# POWER_SUPPLY.net
KiCad netlist of a schematic drawn in Altium Designer
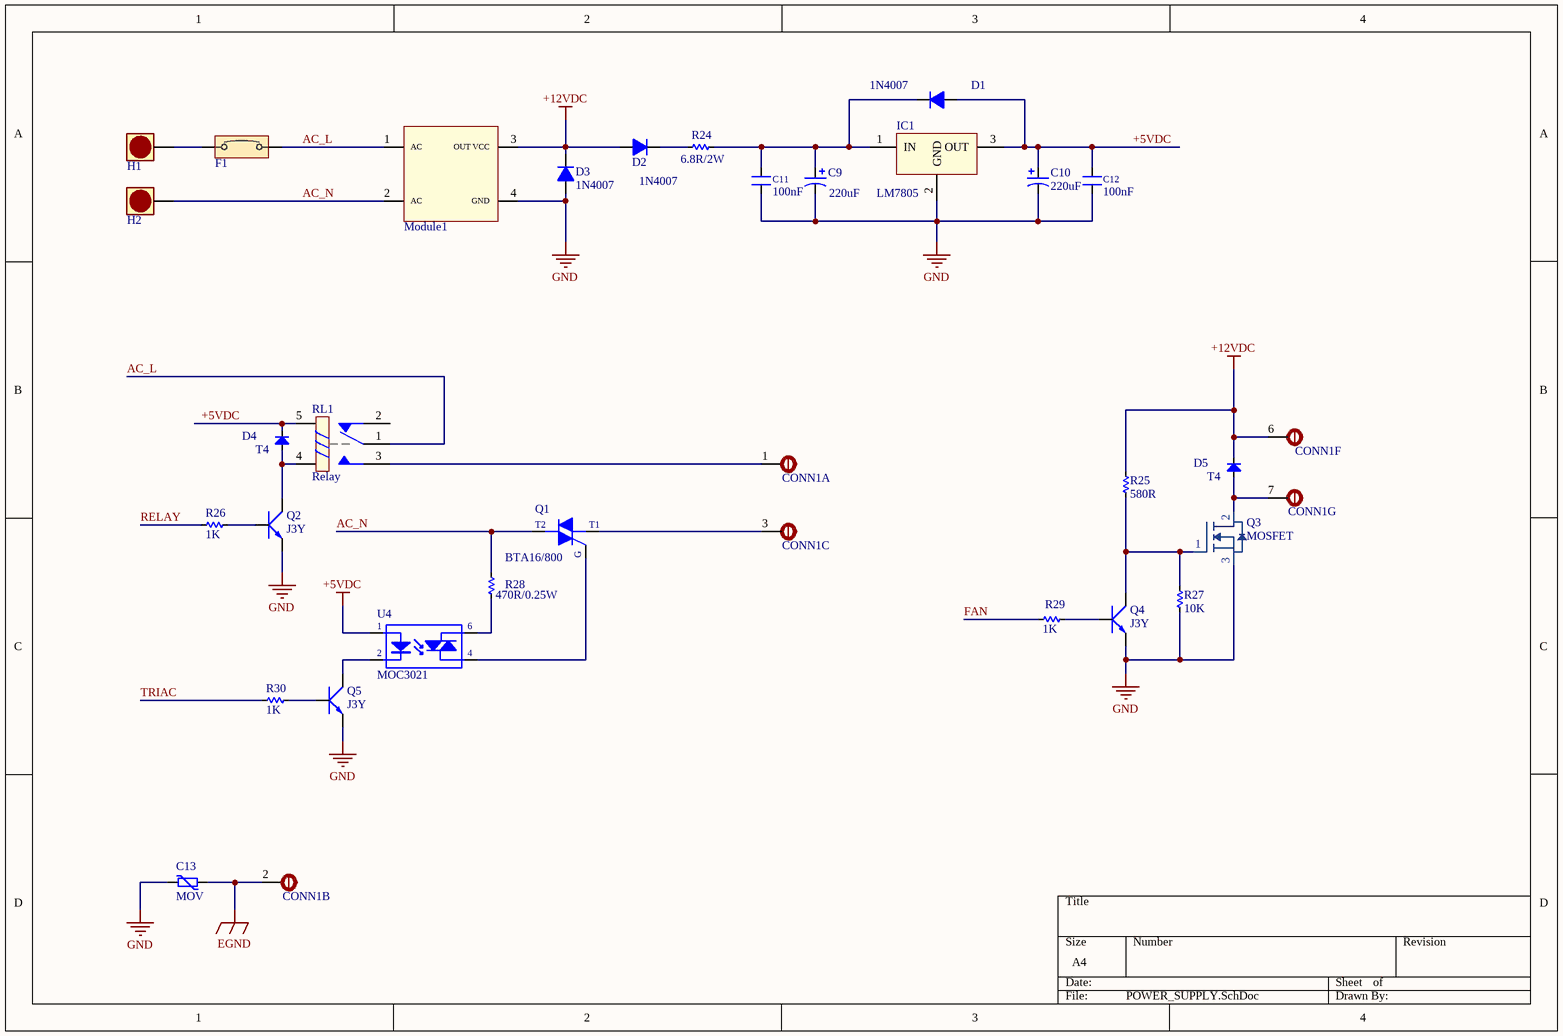
[diagram p0: POWER_SUPPLY.SchDoc]

(export (version "E")
  (design (tool "Eeschema 10.0.6"))
  (components
    (comp (ref "C9")
      (value "220uF")
      (footprint "C8MM")
      (description "CAP-Radial")
      (fields (field (name "PUBLISHER") "Altium Limited"))
      (libsource (lib "") (part "CAP-Radial_1"))
    )
    (comp (ref "C10")
      (value "220uF")
      (footprint "C8MM")
      (description "CAP-Radial")
      (fields (field (name "PUBLISHER") "Altium Limited"))
      (libsource (lib "Sang_Library") (part "CAP-Radial"))
    )
    (comp (ref "C11")
      (value "100nF")
      (footprint "SM-Cap-1206")
      (description "CAP SMD")
      (fields (field (name "DESIGNED BY") "VanDungEvn"))
      (libsource (lib "Sang_Library") (part "CAP SMD"))
    )
    (comp (ref "C12")
      (value "100nF")
      (footprint "SM-Cap-1206")
      (description "CAP SMD")
      (fields (field (name "DESIGNED BY") "VanDungEvn"))
      (libsource (lib "Sang_Library") (part "CAP SMD"))
    )
    (comp (ref "C13") (value "MOV") (footprint "14D271K") (libsource (lib "Huan") (part "MOV")))
    (comp (ref "CONN1")
      (value "GX-16 CONNECTOR")
      (footprint "GX-16")
      (libsource (lib "") (part "GX-16 CONNECTOR_4"))
    )
    (comp (ref "D1")
      (value "1N4007")
      (footprint "DO-213AA")
      (description "Diode 1A")
      (libsource (lib "Sang_Library") (part "Diode  1N4007"))
    )
    (comp (ref "D2")
      (value "1N4007")
      (footprint "DO-213AA")
      (description "Diode 1A")
      (libsource (lib "Sang_Library") (part "Diode  1N4007"))
    )
    (comp (ref "D3")
      (value "1N4007")
      (footprint "DO-213AA")
      (description "Diode 1A")
      (libsource (lib "Sang_Library") (part "Diode  1N4007"))
    )
    (comp (ref "D4")
      (value "T4")
      (footprint "SOD123")
      (description "Default Diode")
      (fields (field (name "PUBLISHER") "Altium Limited"))
      (libsource (lib "Sang_Library") (part "Diode-1N4007 -A4"))
    )
    (comp (ref "D5")
      (value "T4")
      (footprint "SOD123")
      (description "Default Diode")
      (fields (field (name "PUBLISHER") "Altium Limited"))
      (libsource (lib "Sang_Library") (part "Diode-1N4007 -A4"))
    )
    (comp (ref "F1") (value "FUSE") (footprint "FUSE 5X20MM") (libsource (lib "Huan") (part "FUSE")))
    (comp (ref "H1") (value "JP1P") (footprint "PW-JP") (libsource (lib "Huan") (part "JP1P")))
    (comp (ref "H2") (value "JP1P") (footprint "PW-JP") (libsource (lib "Huan") (part "JP1P")))
    (comp (ref "IC1")
      (value "LM7805")
      (footprint "QTO-220H3")
      (description "On ap +, from + 5 to + 24VDC")
      (libsource (lib "Sang_Library") (part "LM78xx"))
    )
    (comp (ref "Module1")
      (value "AC DC Powersupply")
      (footprint "VNPT_ADAPTER")
      (libsource (lib "Huan") (part "AC DC Powersupply"))
    )
    (comp (ref "Q1")
      (value "BTA16/800")
      (footprint "TO220H2")
      (description "Silicon Bidirectional Triode Thyristor")
      (fields (field (name "PUBLISHER") "Altium Limited"))
      (libsource (lib "Sang_Library") (part "BTA12-600_TRIAC"))
    )
    (comp (ref "Q2")
      (value "J3Y")
      (footprint "SOT23B")
      (description "NPN 600mW, ECB")
      (libsource (lib "Sang_Library") (part "2N222"))
    )
    (comp (ref "Q3")
      (value "MOSFET")
      (footprint "TO-252")
      (description "MOSFET N chane")
      (libsource (lib "Huan") (part "MOSFET-N"))
    )
    (comp (ref "Q4")
      (value "J3Y")
      (footprint "SOT23B")
      (description "NPN 600mW, ECB")
      (libsource (lib "Sang_Library") (part "2N222"))
    )
    (comp (ref "Q5")
      (value "J3Y")
      (footprint "SOT23B")
      (description "NPN 600mW, ECB")
      (libsource (lib "Sang_Library") (part "2N222"))
    )
    (comp (ref "R24")
      (value "6.8R/2W")
      (footprint "R2WD")
      (description "Res")
      (fields
        (field (name "MANUFACTURER") "Generic Components")
        (field (name "PUBLISHER") "Altium Hobart Technology Centre")
      )
      (libsource (lib "Sang_Library") (part "Res_DIP"))
    )
    (comp (ref "R25")
      (value "580R")
      (footprint "RES-SMD-0805")
      (description "Resistor")
      (fields
        (field (name "MANUFACTURER") "Generic Components")
        (field (name "PUBLISHER") "Altium Hobart Technology Centre")
      )
      (libsource (lib "Sang_Library") (part "Res-SMD"))
    )
    (comp (ref "R26")
      (value "1K")
      (footprint "RES-SMD-0805")
      (description "Resistor")
      (fields
        (field (name "MANUFACTURER") "Generic Components")
        (field (name "PUBLISHER") "Altium Hobart Technology Centre")
      )
      (libsource (lib "Sang_Library") (part "Res-SMD"))
    )
    (comp (ref "R27")
      (value "10K")
      (footprint "RES-SMD-0603")
      (description "Resistor")
      (fields
        (field (name "MANUFACTURER") "Generic Components")
        (field (name "PUBLISHER") "Altium Hobart Technology Centre")
      )
      (libsource (lib "Sang_Library") (part "Res-SMD"))
    )
    (comp (ref "R28")
      (value "470R/0.25W")
      (footprint "RES-1/4W")
      (description "Res")
      (fields
        (field (name "MANUFACTURER") "Generic Components")
        (field (name "PUBLISHER") "Altium Hobart Technology Centre")
      )
      (libsource (lib "Sang_Library") (part "Res_DIP"))
    )
    (comp (ref "R29")
      (value "1K")
      (footprint "RES-SMD-0805")
      (description "Resistor")
      (fields
        (field (name "MANUFACTURER") "Generic Components")
        (field (name "PUBLISHER") "Altium Hobart Technology Centre")
      )
      (libsource (lib "Sang_Library") (part "Res-SMD"))
    )
    (comp (ref "R30")
      (value "1K")
      (footprint "RES-SMD-0805")
      (description "Resistor")
      (fields
        (field (name "MANUFACTURER") "Generic Components")
        (field (name "PUBLISHER") "Altium Hobart Technology Centre")
      )
      (libsource (lib "Sang_Library") (part "Res-SMD"))
    )
    (comp (ref "RL1")
      (value "Relay")
      (footprint "RL-05VDC-10A")
      (description "Relay SPDT 5 Pin")
      (libsource (lib "Sang_Library") (part "Relay 5VDC"))
    )
    (comp (ref "U4")
      (value "MOC3021")
      (footprint "DIP6/W0.3 - MOC3021")
      (description "Single Opto")
      (libsource (lib "Sang_Library") (part "MOC3021"))
    )
  )
  (nets
    (net (code "1") (name "+5VDC") (class "Default")
      (node (ref "C10") (pin "1") (pinfunction "1_1") (pintype "passive"))
      (node (ref "C12") (pin "1") (pinfunction "1_1") (pintype "passive"))
      (node (ref "D1") (pin "1") (pinfunction "1_1") (pintype "passive"))
      (node (ref "D4") (pin "K") (pinfunction "K_K") (pintype "passive"))
      (node (ref "IC1") (pin "3") (pinfunction "OUT_3") (pintype "passive"))
      (node (ref "RL1") (pin "5") (pinfunction "5_5") (pintype "passive"))
      (node (ref "U4") (pin "1") (pinfunction "A_1") (pintype "passive"))
    )
    (net (code "2") (name "+12VDC") (class "Default")
      (node (ref "CONN1") (pin "6") (pinfunction "6_6") (pintype "passive"))
      (node (ref "D2") (pin "1") (pinfunction "1_1") (pintype "passive"))
      (node (ref "D3") (pin "2") (pinfunction "2_2") (pintype "passive"))
      (node (ref "D5") (pin "K") (pinfunction "K_K") (pintype "passive"))
      (node (ref "Module1") (pin "3") (pinfunction "OUT_VCC_3") (pintype "passive"))
      (node (ref "R25") (pin "1") (pinfunction "1_1") (pintype "passive"))
    )
    (net (code "3") (name "/AC_L") (class "Default")
      (node (ref "F1") (pin "2") (pinfunction "2_2") (pintype "passive"))
      (node (ref "Module1") (pin "1") (pinfunction "AC_1") (pintype "passive"))
      (node (ref "RL1") (pin "1") (pinfunction "1_1") (pintype "passive"))
    )
    (net (code "4") (name "/AC_N") (class "Default")
      (node (ref "H2") (pin "1") (pinfunction "1_1") (pintype "passive"))
      (node (ref "Module1") (pin "2") (pinfunction "AC_2") (pintype "passive"))
      (node (ref "Q1") (pin "2") (pinfunction "M2_2") (pintype "passive"))
      (node (ref "R28") (pin "1") (pinfunction "1_1") (pintype "passive"))
    )
    (net (code "5") (name "/FAN") (class "Default")
      (node (ref "R29") (pin "2") (pinfunction "2_2") (pintype "passive"))
    )
    (net (code "6") (name "/RELAY") (class "Default")
      (node (ref "R26") (pin "2") (pinfunction "2_2") (pintype "passive"))
    )
    (net (code "7") (name "/TRIAC") (class "Default")
      (node (ref "R30") (pin "2") (pinfunction "2_2") (pintype "passive"))
    )
    (net (code "8") (name "EGND") (class "Default")
      (node (ref "C13") (pin "1") (pinfunction "1_1") (pintype "passive"))
      (node (ref "CONN1") (pin "2") (pinfunction "2_2") (pintype "passive"))
    )
    (net (code "9") (name "GND") (class "Default")
      (node (ref "C10") (pin "2") (pinfunction "2_2") (pintype "passive"))
      (node (ref "C11") (pin "2") (pinfunction "2_2") (pintype "passive"))
      (node (ref "C12") (pin "2") (pinfunction "2_2") (pintype "passive"))
      (node (ref "C13") (pin "2") (pinfunction "2_2") (pintype "passive"))
      (node (ref "C9") (pin "2") (pinfunction "2_2") (pintype "passive"))
      (node (ref "D3") (pin "1") (pinfunction "1_1") (pintype "passive"))
      (node (ref "IC1") (pin "2") (pinfunction "GND_2") (pintype "passive"))
      (node (ref "Module1") (pin "4") (pinfunction "GND_4") (pintype "passive"))
      (node (ref "Q2") (pin "1") (pinfunction "E_1") (pintype "passive"))
      (node (ref "Q3") (pin "3") (pinfunction "3_3") (pintype "passive"))
      (node (ref "Q4") (pin "1") (pinfunction "E_1") (pintype "passive"))
      (node (ref "Q5") (pin "1") (pinfunction "E_1") (pintype "passive"))
      (node (ref "R27") (pin "2") (pinfunction "2_2") (pintype "passive"))
    )
    (net (code "10") (name "Net-(CONN1-Pad1)") (class "Default")
      (node (ref "CONN1") (pin "1") (pinfunction "1_1") (pintype "passive"))
      (node (ref "RL1") (pin "3") (pinfunction "3_3") (pintype "passive"))
    )
    (net (code "11") (name "Net-(CONN1-Pad7)") (class "Default")
      (node (ref "CONN1") (pin "7") (pinfunction "7_7") (pintype "passive"))
      (node (ref "D5") (pin "A") (pinfunction "A_A") (pintype "passive"))
      (node (ref "Q3") (pin "2") (pinfunction "2_2") (pintype "passive"))
    )
    (net (code "12") (name "Net-(D2-Pad2)") (class "Default")
      (node (ref "D2") (pin "2") (pinfunction "2_2") (pintype "passive"))
      (node (ref "R24") (pin "2") (pinfunction "2_2") (pintype "passive"))
    )
    (net (code "13") (name "Net-(F1-Pad1)") (class "Default")
      (node (ref "F1") (pin "1") (pinfunction "1_1") (pintype "passive"))
      (node (ref "H1") (pin "1") (pinfunction "1_1") (pintype "passive"))
    )
    (net (code "14") (name "Net-(IC1-IN)") (class "Default")
      (node (ref "C11") (pin "1") (pinfunction "1_1") (pintype "passive"))
      (node (ref "C9") (pin "1") (pinfunction "1_1") (pintype "passive"))
      (node (ref "D1") (pin "2") (pinfunction "2_2") (pintype "passive"))
      (node (ref "IC1") (pin "1") (pinfunction "IN_1") (pintype "passive"))
      (node (ref "R24") (pin "1") (pinfunction "1_1") (pintype "passive"))
    )
    (net (code "15") (name "Net-(Q1-G)") (class "Default")
      (node (ref "Q1") (pin "3") (pinfunction "G_3") (pintype "passive"))
      (node (ref "U4") (pin "4") (pinfunction "E_4") (pintype "passive"))
    )
    (net (code "16") (name "Net-(Q1-M1)") (class "Default")
      (node (ref "CONN1") (pin "3") (pinfunction "3_3") (pintype "passive"))
      (node (ref "Q1") (pin "1") (pinfunction "M1_1") (pintype "passive"))
    )
    (net (code "17") (name "Net-(Q2-B)") (class "Default")
      (node (ref "Q2") (pin "2") (pinfunction "B_2") (pintype "passive"))
      (node (ref "R26") (pin "1") (pinfunction "1_1") (pintype "passive"))
    )
    (net (code "18") (name "Net-(Q2-C)") (class "Default")
      (node (ref "D4") (pin "A") (pinfunction "A_A") (pintype "passive"))
      (node (ref "Q2") (pin "3") (pinfunction "C_3") (pintype "passive"))
      (node (ref "RL1") (pin "4") (pinfunction "4_4") (pintype "passive"))
    )
    (net (code "19") (name "Net-(Q4-B)") (class "Default")
      (node (ref "Q4") (pin "2") (pinfunction "B_2") (pintype "passive"))
      (node (ref "R29") (pin "1") (pinfunction "1_1") (pintype "passive"))
    )
    (net (code "20") (name "Net-(Q4-C)") (class "Default")
      (node (ref "Q3") (pin "1") (pinfunction "1_1") (pintype "passive"))
      (node (ref "Q4") (pin "3") (pinfunction "C_3") (pintype "passive"))
      (node (ref "R25") (pin "2") (pinfunction "2_2") (pintype "passive"))
      (node (ref "R27") (pin "1") (pinfunction "1_1") (pintype "passive"))
    )
    (net (code "21") (name "Net-(Q5-B)") (class "Default")
      (node (ref "Q5") (pin "2") (pinfunction "B_2") (pintype "passive"))
      (node (ref "R30") (pin "1") (pinfunction "1_1") (pintype "passive"))
    )
    (net (code "22") (name "Net-(Q5-C)") (class "Default")
      (node (ref "Q5") (pin "3") (pinfunction "C_3") (pintype "passive"))
      (node (ref "U4") (pin "2") (pinfunction "K_2") (pintype "passive"))
    )
    (net (code "23") (name "Net-(U4-C)") (class "Default")
      (node (ref "R28") (pin "2") (pinfunction "2_2") (pintype "passive"))
      (node (ref "U4") (pin "6") (pinfunction "C_6") (pintype "passive"))
    )
    (net (code "24") (name "unconnected-(RL1-Pad2)") (class "Default")
      (node (ref "RL1") (pin "2") (pinfunction "2_2") (pintype "passive"))
    )
  )
)
